# Reefing-PD.net
KiCad netlist of a schematic drawn in Altium Designer
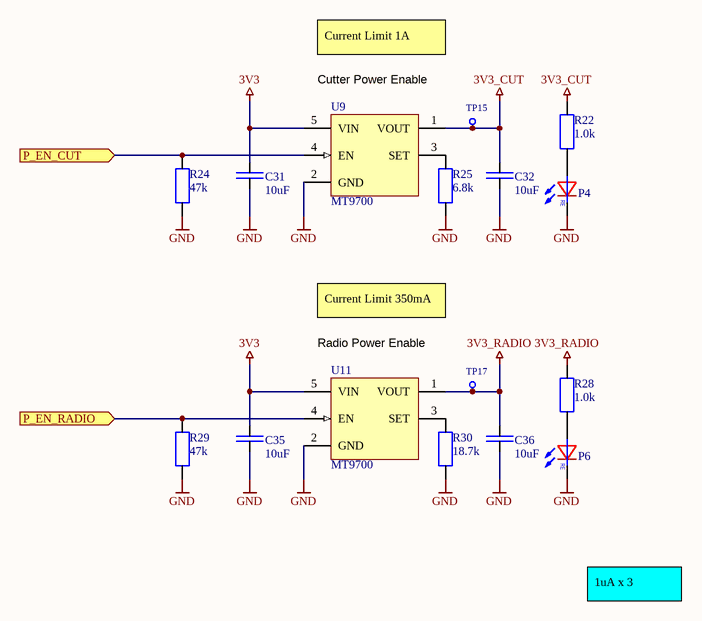
[diagram p0: Reefing-PD.SchDoc]

(export (version "E")
  (design (tool "Eeschema 10.0.6"))
  (components
    (comp (ref "C31")
      (value "10uF")
      (footprint "SMD Keramikkondensator 0603")
      (description "SMD Ceramic Capacitor E6")
      (libsource (lib "Ceramic Capacitors-E6") (part "E6 - 10uF"))
    )
    (comp (ref "C32")
      (value "10uF")
      (footprint "SMD Keramikkondensator 0603")
      (description "SMD Ceramic Capacitor E6")
      (libsource (lib "Ceramic Capacitors-E6") (part "E6 - 10uF"))
    )
    (comp (ref "C35")
      (value "10uF")
      (footprint "SMD Keramikkondensator 0603")
      (description "SMD Ceramic Capacitor E6")
      (libsource (lib "Ceramic Capacitors-E6") (part "E6 - 10uF"))
    )
    (comp (ref "C36")
      (value "10uF")
      (footprint "SMD Keramikkondensator 0603")
      (description "SMD Ceramic Capacitor E6")
      (libsource (lib "Ceramic Capacitors-E6") (part "E6 - 10uF"))
    )
    (comp (ref "P4")
      (value "LED")
      (footprint "SMD LED 0603")
      (description "Color LED")
      (libsource (lib "Diodes") (part "LED"))
    )
    (comp (ref "P6")
      (value "LED")
      (footprint "SMD LED 0603")
      (description "Color LED")
      (libsource (lib "Diodes") (part "LED"))
    )
    (comp (ref "R22")
      (value "1.0k")
      (footprint "SMD Widerstand 0402")
      (description "SMD Chip Resistor E24")
      (libsource (lib "Resistors-E24") (part "E24 - 1.0k"))
    )
    (comp (ref "R24")
      (value "47k")
      (footprint "SMD Widerstand 0402")
      (description "SMD Chip Resistor E24")
      (libsource (lib "Resistors-E24") (part "E24 - 47k"))
    )
    (comp (ref "R25")
      (value "6.8k")
      (footprint "SMD Widerstand 0402")
      (description "SMD Chip Resistor E24")
      (libsource (lib "Resistors-E24") (part "E24 - 6.8k"))
    )
    (comp (ref "R28")
      (value "1.0k")
      (footprint "SMD Widerstand 0402")
      (description "SMD Chip Resistor E24")
      (libsource (lib "Resistors-E24") (part "E24 - 1.0k"))
    )
    (comp (ref "R29")
      (value "47k")
      (footprint "SMD Widerstand 0402")
      (description "SMD Chip Resistor E24")
      (libsource (lib "Resistors-E24") (part "E24 - 47k"))
    )
    (comp (ref "R30")
      (value "18.7k")
      (footprint "SMD Widerstand 0402")
      (description "SMD Chip Resistor E96")
      (libsource (lib "Resistors-E96") (part "E96 - 18.7k"))
    )
    (comp (ref "TP15")
      (value "X-TP")
      (footprint "SMD Testpoint 1mm")
      (description "Testpunkt")
      (libsource (lib "Fleet-Monitor") (part "X-TP"))
    )
    (comp (ref "TP17")
      (value "X-TP")
      (footprint "SMD Testpoint 1mm")
      (description "Testpunkt")
      (libsource (lib "Fleet-Monitor") (part "X-TP"))
    )
    (comp (ref "U9")
      (value "MT9700")
      (footprint "SMD IC SOT-23-5")
      (description "Power Distribution Switch")
      (libsource (lib "Electronic Switches") (part "MT9700"))
    )
    (comp (ref "U11")
      (value "MT9700")
      (footprint "SMD IC SOT-23-5")
      (description "Power Distribution Switch")
      (libsource (lib "Electronic Switches") (part "MT9700"))
    )
  )
  (nets
    (net (code "1") (name "/P_EN_CUT") (class "Default")
      (node (ref "R24") (pin "2") (pinfunction "2_2") (pintype "passive"))
      (node (ref "U9") (pin "4") (pinfunction "EN_4") (pintype "input"))
    )
    (net (code "2") (name "/P_EN_RADIO") (class "Default")
      (node (ref "R29") (pin "2") (pinfunction "2_2") (pintype "passive"))
      (node (ref "U11") (pin "4") (pinfunction "EN_4") (pintype "input"))
    )
    (net (code "3") (name "3V3") (class "Default")
      (node (ref "C31") (pin "2") (pinfunction "2_2") (pintype "passive"))
      (node (ref "C35") (pin "2") (pinfunction "2_2") (pintype "passive"))
      (node (ref "U11") (pin "5") (pinfunction "VIN_5") (pintype "passive"))
      (node (ref "U9") (pin "5") (pinfunction "VIN_5") (pintype "passive"))
    )
    (net (code "4") (name "3V3_CUT") (class "Default")
      (node (ref "C32") (pin "2") (pinfunction "2_2") (pintype "passive"))
      (node (ref "R22") (pin "2") (pinfunction "2_2") (pintype "passive"))
      (node (ref "TP15") (pin "1") (pinfunction "1_1") (pintype "passive"))
      (node (ref "U9") (pin "1") (pinfunction "VOUT_1") (pintype "passive"))
    )
    (net (code "5") (name "3V3_RADIO") (class "Default")
      (node (ref "C36") (pin "2") (pinfunction "2_2") (pintype "passive"))
      (node (ref "R28") (pin "2") (pinfunction "2_2") (pintype "passive"))
      (node (ref "TP17") (pin "1") (pinfunction "1_1") (pintype "passive"))
      (node (ref "U11") (pin "1") (pinfunction "VOUT_1") (pintype "passive"))
    )
    (net (code "6") (name "GND") (class "Default")
      (node (ref "C31") (pin "1") (pinfunction "1_1") (pintype "passive"))
      (node (ref "C32") (pin "1") (pinfunction "1_1") (pintype "passive"))
      (node (ref "C35") (pin "1") (pinfunction "1_1") (pintype "passive"))
      (node (ref "C36") (pin "1") (pinfunction "1_1") (pintype "passive"))
      (node (ref "P4") (pin "K") (pinfunction "K_K") (pintype "passive"))
      (node (ref "P6") (pin "K") (pinfunction "K_K") (pintype "passive"))
      (node (ref "R24") (pin "1") (pinfunction "1_1") (pintype "passive"))
      (node (ref "R25") (pin "1") (pinfunction "1_1") (pintype "passive"))
      (node (ref "R29") (pin "1") (pinfunction "1_1") (pintype "passive"))
      (node (ref "R30") (pin "1") (pinfunction "1_1") (pintype "passive"))
      (node (ref "U11") (pin "2") (pinfunction "GND_2") (pintype "passive"))
      (node (ref "U9") (pin "2") (pinfunction "GND_2") (pintype "passive"))
    )
    (net (code "7") (name "Net-(P4-PadA)") (class "Default")
      (node (ref "P4") (pin "A") (pinfunction "A_A") (pintype "passive"))
      (node (ref "R22") (pin "1") (pinfunction "1_1") (pintype "passive"))
    )
    (net (code "8") (name "Net-(P6-PadA)") (class "Default")
      (node (ref "P6") (pin "A") (pinfunction "A_A") (pintype "passive"))
      (node (ref "R28") (pin "1") (pinfunction "1_1") (pintype "passive"))
    )
    (net (code "9") (name "Net-(U9-SET)") (class "Default")
      (node (ref "R25") (pin "2") (pinfunction "2_2") (pintype "passive"))
      (node (ref "U9") (pin "3") (pinfunction "SET_3") (pintype "passive"))
    )
    (net (code "10") (name "Net-(U11-SET)") (class "Default")
      (node (ref "R30") (pin "2") (pinfunction "2_2") (pintype "passive"))
      (node (ref "U11") (pin "3") (pinfunction "SET_3") (pintype "passive"))
    )
  )
)
